# v2car.net
KiCad netlist of a schematic drawn in Altium Designer
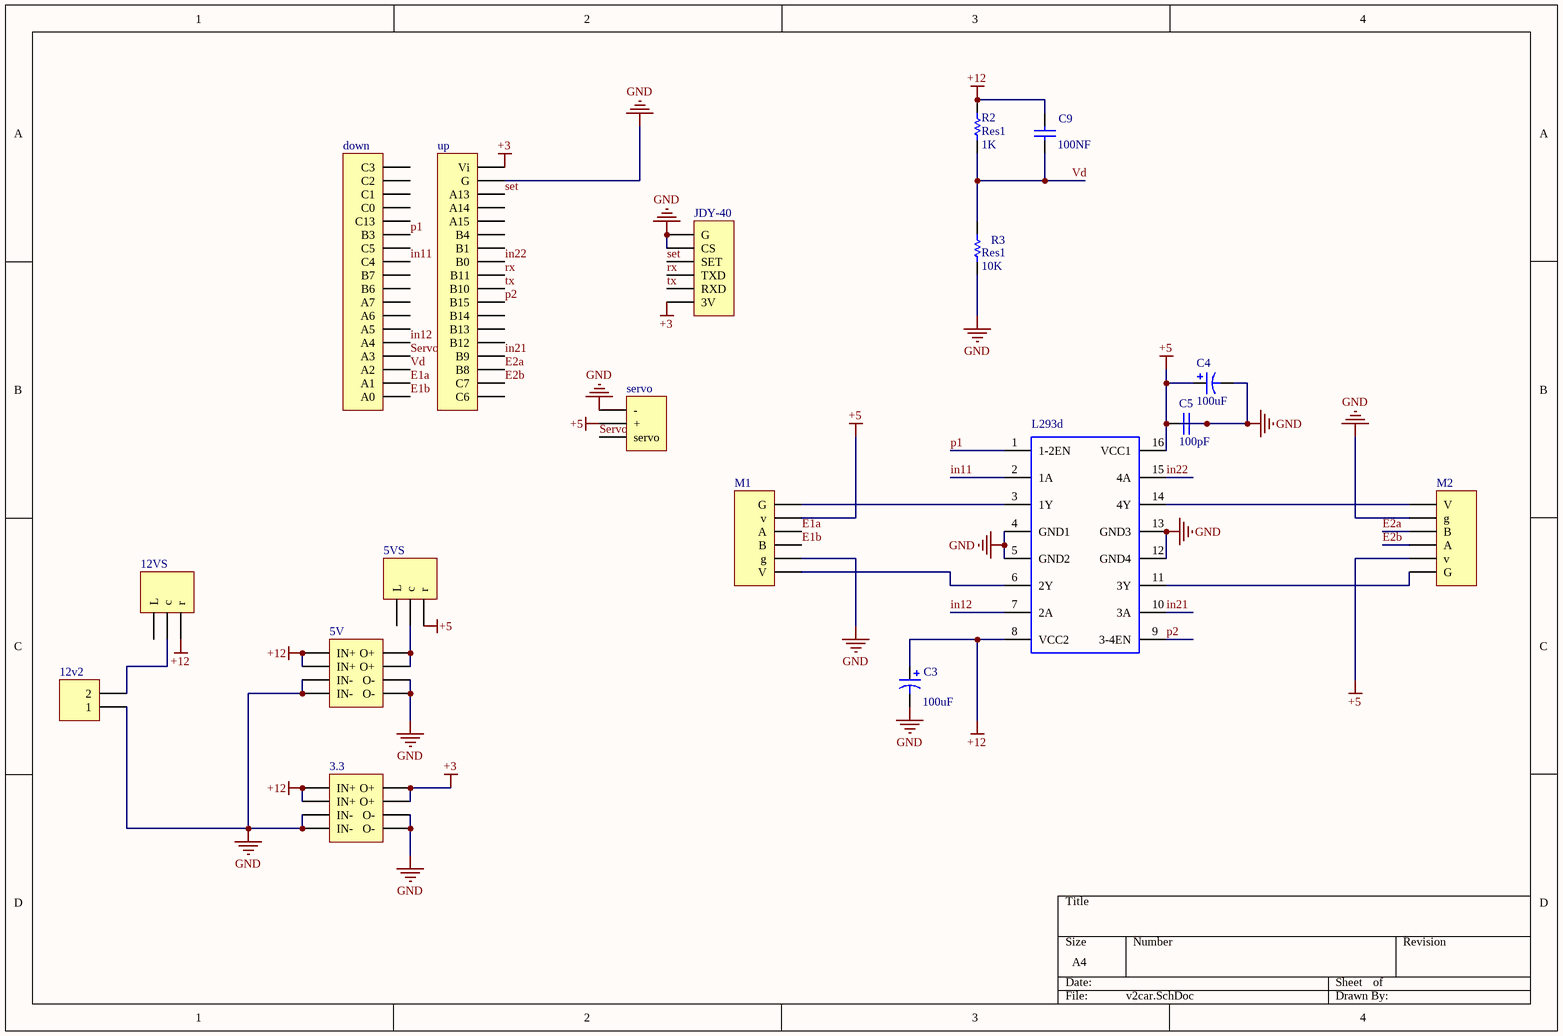
[diagram p0: v2car.SchDoc]

(export (version "E")
  (design (tool "Eeschema 10.0.6"))
  (components
    (comp (ref "3.3")
      (value "Header 4X2")
      (footprint "power:PCBComponent_1")
      (description "Header, 4-Pin, Dual row")
      (fields (field (name "PUBLISHER") "Altium Limited"))
      (libsource (lib "Miscellaneous Connectors") (part "Header 4X2"))
    )
    (comp (ref "5V")
      (value "Header 4X2")
      (footprint "power:PCBComponent_1")
      (description "Header, 4-Pin, Dual row")
      (fields (field (name "PUBLISHER") "Altium Limited"))
      (libsource (lib "Miscellaneous Connectors") (part "Header 4X2"))
    )
    (comp (ref "5VS")
      (value "Header 3")
      (footprint "HDR1X3")
      (description "Header, 3-Pin")
      (fields (field (name "PUBLISHER") "Altium Limited"))
      (libsource (lib "Miscellaneous Connectors") (part "Header 3"))
    )
    (comp (ref "12v2")
      (value "Header 2")
      (footprint "HDR1X2")
      (description "Header, 2-Pin")
      (fields (field (name "PUBLISHER") "Altium Limited"))
      (libsource (lib "Miscellaneous Connectors") (part "Header 2"))
    )
    (comp (ref "12VS")
      (value "Header 3")
      (footprint "HDR1X3")
      (description "Header, 3-Pin")
      (fields (field (name "PUBLISHER") "Altium Limited"))
      (libsource (lib "Miscellaneous Connectors") (part "Header 3"))
    )
    (comp (ref "C3")
      (value "100uF")
      (footprint "贴片:0805")
      (description "Polarized Capacitor (Radial)")
      (fields (field (name "Comment") "Cap Pol1") (field (name "PUBLISHER") "Altium Limited"))
      (libsource (lib "Miscellaneous Devices") (part "Cap Pol1"))
    )
    (comp (ref "C4")
      (value "100uF")
      (footprint "贴片:0805")
      (description "Polarized Capacitor (Radial)")
      (fields (field (name "Comment") "Cap Pol1") (field (name "PUBLISHER") "Altium Limited"))
      (libsource (lib "Miscellaneous Devices") (part "Cap Pol1"))
    )
    (comp (ref "C5")
      (value "100pF")
      (footprint "贴片:0805")
      (description "Capacitor")
      (fields (field (name "Comment") "Cap") (field (name "PUBLISHER") "Altium Limited"))
      (libsource (lib "Miscellaneous Devices") (part "Cap"))
    )
    (comp (ref "C9")
      (value "100NF")
      (footprint "贴片:0805")
      (description "Capacitor")
      (fields (field (name "Comment") "Cap") (field (name "PUBLISHER") "Altium Limited"))
      (libsource (lib "Miscellaneous Devices") (part "Cap"))
    )
    (comp (ref "down")
      (value "Header 18H")
      (footprint "HDR1X18")
      (description "Header, 18-Pin, Right Angle")
      (fields (field (name "PUBLISHER") "Altium Limited"))
      (libsource (lib "Miscellaneous Connectors") (part "Header 18H"))
    )
    (comp (ref "JDY-40")
      (value "MHDR1X6")
      (footprint "JDY-40.~(1):JDY-401")
      (description "Header, 6-Pin")
      (fields (field (name "PUBLISHER") "Altium Limited"))
      (libsource (lib "xcar") (part "MHDR1X6"))
    )
    (comp (ref "L293d") (value "~") (footprint "L20:PCBComponent_1") (libsource (lib "texas") (part "L293E")))
    (comp (ref "M1")
      (value "Header 6")
      (footprint "M:PCBComponent_1")
      (description "Header, 6-Pin")
      (fields (field (name "PUBLISHER") "Altium Limited"))
      (libsource (lib "") (part "Header 6_1"))
    )
    (comp (ref "M2")
      (value "Header 6")
      (footprint "M:PCBComponent_1")
      (description "Header, 6-Pin")
      (fields (field (name "PUBLISHER") "Altium Limited"))
      (libsource (lib "Miscellaneous Connectors") (part "Header 6"))
    )
    (comp (ref "R2")
      (value "Res1")
      (footprint "贴片:0805")
      (description "Resistor")
      (fields (field (name "ALTIUM_VALUE") "1K") (field (name "PUBLISHER") "Altium Limited"))
      (libsource (lib "Miscellaneous Devices") (part "Res1"))
    )
    (comp (ref "R3")
      (value "Res1")
      (footprint "贴片:0805")
      (description "Resistor")
      (fields (field (name "ALTIUM_VALUE") "10K") (field (name "PUBLISHER") "Altium Limited"))
      (libsource (lib "Miscellaneous Devices") (part "Res1"))
    )
    (comp (ref "servo")
      (value "Header 3")
      (footprint "HDR1X3")
      (description "Header, 3-Pin")
      (fields (field (name "PUBLISHER") "Altium Limited"))
      (libsource (lib "") (part "Header 3_1"))
    )
    (comp (ref "up")
      (value "Header 18")
      (footprint "HDR1X18")
      (description "Header, 18-Pin")
      (fields (field (name "PUBLISHER") "Altium Limited"))
      (libsource (lib "Miscellaneous Connectors") (part "Header 18"))
    )
  )
  (nets
    (net (code "1") (name "+3") (class "Default")
      (node (ref "3.3") (pin "2") (pinfunction "O+_2") (pintype "passive"))
      (node (ref "3.3") (pin "4") (pinfunction "O+_4") (pintype "passive"))
      (node (ref "JDY-40") (pin "6") (pinfunction "3V_6") (pintype "passive"))
      (node (ref "up") (pin "18") (pinfunction "Vi_18") (pintype "passive"))
    )
    (net (code "2") (name "+5") (class "Default")
      (node (ref "5VS") (pin "3") (pinfunction "r_3") (pintype "passive"))
      (node (ref "C4") (pin "1") (pinfunction "1_1") (pintype "passive"))
      (node (ref "C5") (pin "2") (pinfunction "2_2") (pintype "passive"))
      (node (ref "L293d") (pin "16") (pinfunction "VCC1_16") (pintype "passive"))
      (node (ref "M1") (pin "5") (pinfunction "v_5") (pintype "passive"))
      (node (ref "M2") (pin "5") (pinfunction "v_5") (pintype "passive"))
      (node (ref "servo") (pin "2") (pinfunction "+_2") (pintype "passive"))
    )
    (net (code "3") (name "+12") (class "Default")
      (node (ref "12VS") (pin "3") (pinfunction "r_3") (pintype "passive"))
      (node (ref "3.3") (pin "1") (pinfunction "IN+_1") (pintype "passive"))
      (node (ref "3.3") (pin "3") (pinfunction "IN+_3") (pintype "passive"))
      (node (ref "5V") (pin "1") (pinfunction "IN+_1") (pintype "passive"))
      (node (ref "5V") (pin "3") (pinfunction "IN+_3") (pintype "passive"))
      (node (ref "C3") (pin "1") (pinfunction "1_1") (pintype "passive"))
      (node (ref "C9") (pin "1") (pinfunction "1_1") (pintype "passive"))
      (node (ref "L293d") (pin "8") (pinfunction "VCC2_8") (pintype "passive"))
      (node (ref "R2") (pin "2") (pinfunction "2_2") (pintype "passive"))
    )
    (net (code "4") (name "/E1a") (class "Default")
      (node (ref "M1") (pin "4") (pinfunction "A_4") (pintype "passive"))
      (node (ref "down") (pin "2") (pinfunction "A1_2") (pintype "passive"))
    )
    (net (code "5") (name "/E1b") (class "Default")
      (node (ref "M1") (pin "3") (pinfunction "B_3") (pintype "passive"))
      (node (ref "down") (pin "1") (pinfunction "A0_1") (pintype "passive"))
    )
    (net (code "6") (name "/E2a") (class "Default")
      (node (ref "M2") (pin "3") (pinfunction "B_3") (pintype "passive"))
      (node (ref "up") (pin "3") (pinfunction "B8_3") (pintype "passive"))
    )
    (net (code "7") (name "/E2b") (class "Default")
      (node (ref "M2") (pin "4") (pinfunction "A_4") (pintype "passive"))
      (node (ref "up") (pin "2") (pinfunction "C7_2") (pintype "passive"))
    )
    (net (code "8") (name "/Servo") (class "Default")
      (node (ref "down") (pin "4") (pinfunction "A3_4") (pintype "passive"))
      (node (ref "servo") (pin "3") (pinfunction "servo_3") (pintype "passive"))
    )
    (net (code "9") (name "/Vd") (class "Default")
      (node (ref "C9") (pin "2") (pinfunction "2_2") (pintype "passive"))
      (node (ref "R2") (pin "1") (pinfunction "1_1") (pintype "passive"))
      (node (ref "R3") (pin "2") (pinfunction "2_2") (pintype "passive"))
      (node (ref "down") (pin "3") (pinfunction "A2_3") (pintype "passive"))
    )
    (net (code "10") (name "/in11") (class "Default")
      (node (ref "L293d") (pin "2") (pinfunction "1A_2") (pintype "passive"))
      (node (ref "down") (pin "11") (pinfunction "C4_11") (pintype "passive"))
    )
    (net (code "11") (name "/in12") (class "Default")
      (node (ref "L293d") (pin "7") (pinfunction "2A_7") (pintype "passive"))
      (node (ref "down") (pin "5") (pinfunction "A4_5") (pintype "passive"))
    )
    (net (code "12") (name "/in21") (class "Default")
      (node (ref "L293d") (pin "10") (pinfunction "3A_10") (pintype "passive"))
      (node (ref "up") (pin "4") (pinfunction "B9_4") (pintype "passive"))
    )
    (net (code "13") (name "/in22") (class "Default")
      (node (ref "L293d") (pin "15") (pinfunction "4A_15") (pintype "passive"))
      (node (ref "up") (pin "11") (pinfunction "B0_11") (pintype "passive"))
    )
    (net (code "14") (name "/p1") (class "Default")
      (node (ref "L293d") (pin "1") (pinfunction "1-2EN_1") (pintype "passive"))
      (node (ref "down") (pin "13") (pinfunction "B3_13") (pintype "passive"))
    )
    (net (code "15") (name "/p2") (class "Default")
      (node (ref "L293d") (pin "9") (pinfunction "3-4EN_9") (pintype "passive"))
      (node (ref "up") (pin "8") (pinfunction "B15_8") (pintype "passive"))
    )
    (net (code "16") (name "/rx") (class "Default")
      (node (ref "JDY-40") (pin "4") (pinfunction "TXD_4") (pintype "passive"))
      (node (ref "up") (pin "10") (pinfunction "B11_10") (pintype "passive"))
    )
    (net (code "17") (name "/set") (class "Default")
      (node (ref "JDY-40") (pin "3") (pinfunction "SET_3") (pintype "passive"))
      (node (ref "up") (pin "16") (pinfunction "A13_16") (pintype "passive"))
    )
    (net (code "18") (name "/tx") (class "Default")
      (node (ref "JDY-40") (pin "5") (pinfunction "RXD_5") (pintype "passive"))
      (node (ref "up") (pin "9") (pinfunction "B10_9") (pintype "passive"))
    )
    (net (code "19") (name "GND") (class "Default")
      (node (ref "12v2") (pin "1") (pinfunction "1_1") (pintype "passive"))
      (node (ref "3.3") (pin "5") (pinfunction "IN-_5") (pintype "passive"))
      (node (ref "3.3") (pin "6") (pinfunction "O-_6") (pintype "passive"))
      (node (ref "3.3") (pin "7") (pinfunction "IN-_7") (pintype "passive"))
      (node (ref "3.3") (pin "8") (pinfunction "O-_8") (pintype "passive"))
      (node (ref "5V") (pin "5") (pinfunction "IN-_5") (pintype "passive"))
      (node (ref "5V") (pin "6") (pinfunction "O-_6") (pintype "passive"))
      (node (ref "5V") (pin "7") (pinfunction "IN-_7") (pintype "passive"))
      (node (ref "5V") (pin "8") (pinfunction "O-_8") (pintype "passive"))
      (node (ref "C3") (pin "2") (pinfunction "2_2") (pintype "passive"))
      (node (ref "C4") (pin "2") (pinfunction "2_2") (pintype "passive"))
      (node (ref "C5") (pin "1") (pinfunction "1_1") (pintype "passive"))
      (node (ref "JDY-40") (pin "1") (pinfunction "G_1") (pintype "passive"))
      (node (ref "JDY-40") (pin "2") (pinfunction "CS_2") (pintype "passive"))
      (node (ref "L293d") (pin "12") (pinfunction "GND4_12") (pintype "passive"))
      (node (ref "L293d") (pin "13") (pinfunction "GND3_13") (pintype "passive"))
      (node (ref "L293d") (pin "4") (pinfunction "GND1_4") (pintype "passive"))
      (node (ref "L293d") (pin "5") (pinfunction "GND2_5") (pintype "passive"))
      (node (ref "M1") (pin "2") (pinfunction "g_2") (pintype "passive"))
      (node (ref "M2") (pin "2") (pinfunction "g_2") (pintype "passive"))
      (node (ref "R3") (pin "1") (pinfunction "1_1") (pintype "passive"))
      (node (ref "servo") (pin "1") (pinfunction "-_1") (pintype "passive"))
      (node (ref "up") (pin "17") (pinfunction "G_17") (pintype "passive"))
    )
    (net (code "20") (name "Net-(5VS-c)") (class "Default")
      (node (ref "5V") (pin "2") (pinfunction "O+_2") (pintype "passive"))
      (node (ref "5V") (pin "4") (pinfunction "O+_4") (pintype "passive"))
      (node (ref "5VS") (pin "2") (pinfunction "c_2") (pintype "passive"))
    )
    (net (code "21") (name "Net-(12VS-c)") (class "Default")
      (node (ref "12VS") (pin "2") (pinfunction "c_2") (pintype "passive"))
      (node (ref "12v2") (pin "2") (pinfunction "2_2") (pintype "passive"))
    )
    (net (code "22") (name "Net-(L293d-1Y)") (class "Default")
      (node (ref "L293d") (pin "3") (pinfunction "1Y_3") (pintype "passive"))
      (node (ref "M1") (pin "6") (pinfunction "G_6") (pintype "passive"))
    )
    (net (code "23") (name "Net-(L293d-2Y)") (class "Default")
      (node (ref "L293d") (pin "6") (pinfunction "2Y_6") (pintype "passive"))
      (node (ref "M1") (pin "1") (pinfunction "V_1") (pintype "passive"))
    )
    (net (code "24") (name "Net-(L293d-3Y)") (class "Default")
      (node (ref "L293d") (pin "11") (pinfunction "3Y_11") (pintype "passive"))
      (node (ref "M2") (pin "6") (pinfunction "G_6") (pintype "passive"))
    )
    (net (code "25") (name "Net-(L293d-4Y)") (class "Default")
      (node (ref "L293d") (pin "14") (pinfunction "4Y_14") (pintype "passive"))
      (node (ref "M2") (pin "1") (pinfunction "V_1") (pintype "passive"))
    )
    (net (code "26") (name "unconnected-(5VS-L-Pad1)") (class "Default")
      (node (ref "5VS") (pin "1") (pinfunction "L_1") (pintype "passive"))
    )
    (net (code "27") (name "unconnected-(12VS-L-Pad1)") (class "Default")
      (node (ref "12VS") (pin "1") (pinfunction "L_1") (pintype "passive"))
    )
    (net (code "28") (name "unconnected-(down-A5-Pad6)") (class "Default")
      (node (ref "down") (pin "6") (pinfunction "A5_6") (pintype "passive"))
    )
    (net (code "29") (name "unconnected-(down-A6-Pad7)") (class "Default")
      (node (ref "down") (pin "7") (pinfunction "A6_7") (pintype "passive"))
    )
    (net (code "30") (name "unconnected-(down-A7-Pad8)") (class "Default")
      (node (ref "down") (pin "8") (pinfunction "A7_8") (pintype "passive"))
    )
    (net (code "31") (name "unconnected-(down-B6-Pad9)") (class "Default")
      (node (ref "down") (pin "9") (pinfunction "B6_9") (pintype "passive"))
    )
    (net (code "32") (name "unconnected-(down-B7-Pad10)") (class "Default")
      (node (ref "down") (pin "10") (pinfunction "B7_10") (pintype "passive"))
    )
    (net (code "33") (name "unconnected-(down-C0-Pad15)") (class "Default")
      (node (ref "down") (pin "15") (pinfunction "C0_15") (pintype "passive"))
    )
    (net (code "34") (name "unconnected-(down-C1-Pad16)") (class "Default")
      (node (ref "down") (pin "16") (pinfunction "C1_16") (pintype "passive"))
    )
    (net (code "35") (name "unconnected-(down-C2-Pad17)") (class "Default")
      (node (ref "down") (pin "17") (pinfunction "C2_17") (pintype "passive"))
    )
    (net (code "36") (name "unconnected-(down-C3-Pad18)") (class "Default")
      (node (ref "down") (pin "18") (pinfunction "C3_18") (pintype "passive"))
    )
    (net (code "37") (name "unconnected-(down-C5-Pad12)") (class "Default")
      (node (ref "down") (pin "12") (pinfunction "C5_12") (pintype "passive"))
    )
    (net (code "38") (name "unconnected-(down-C13-Pad14)") (class "Default")
      (node (ref "down") (pin "14") (pinfunction "C13_14") (pintype "passive"))
    )
    (net (code "39") (name "unconnected-(up-A14-Pad15)") (class "Default")
      (node (ref "up") (pin "15") (pinfunction "A14_15") (pintype "passive"))
    )
    (net (code "40") (name "unconnected-(up-A15-Pad14)") (class "Default")
      (node (ref "up") (pin "14") (pinfunction "A15_14") (pintype "passive"))
    )
    (net (code "41") (name "unconnected-(up-B1-Pad12)") (class "Default")
      (node (ref "up") (pin "12") (pinfunction "B1_12") (pintype "passive"))
    )
    (net (code "42") (name "unconnected-(up-B4-Pad13)") (class "Default")
      (node (ref "up") (pin "13") (pinfunction "B4_13") (pintype "passive"))
    )
    (net (code "43") (name "unconnected-(up-B12-Pad5)") (class "Default")
      (node (ref "up") (pin "5") (pinfunction "B12_5") (pintype "passive"))
    )
    (net (code "44") (name "unconnected-(up-B13-Pad6)") (class "Default")
      (node (ref "up") (pin "6") (pinfunction "B13_6") (pintype "passive"))
    )
    (net (code "45") (name "unconnected-(up-B14-Pad7)") (class "Default")
      (node (ref "up") (pin "7") (pinfunction "B14_7") (pintype "passive"))
    )
    (net (code "46") (name "unconnected-(up-C6-Pad1)") (class "Default")
      (node (ref "up") (pin "1") (pinfunction "C6_1") (pintype "passive"))
    )
  )
)
